# Sensores.net
KiCad netlist of a schematic drawn in Altium Designer
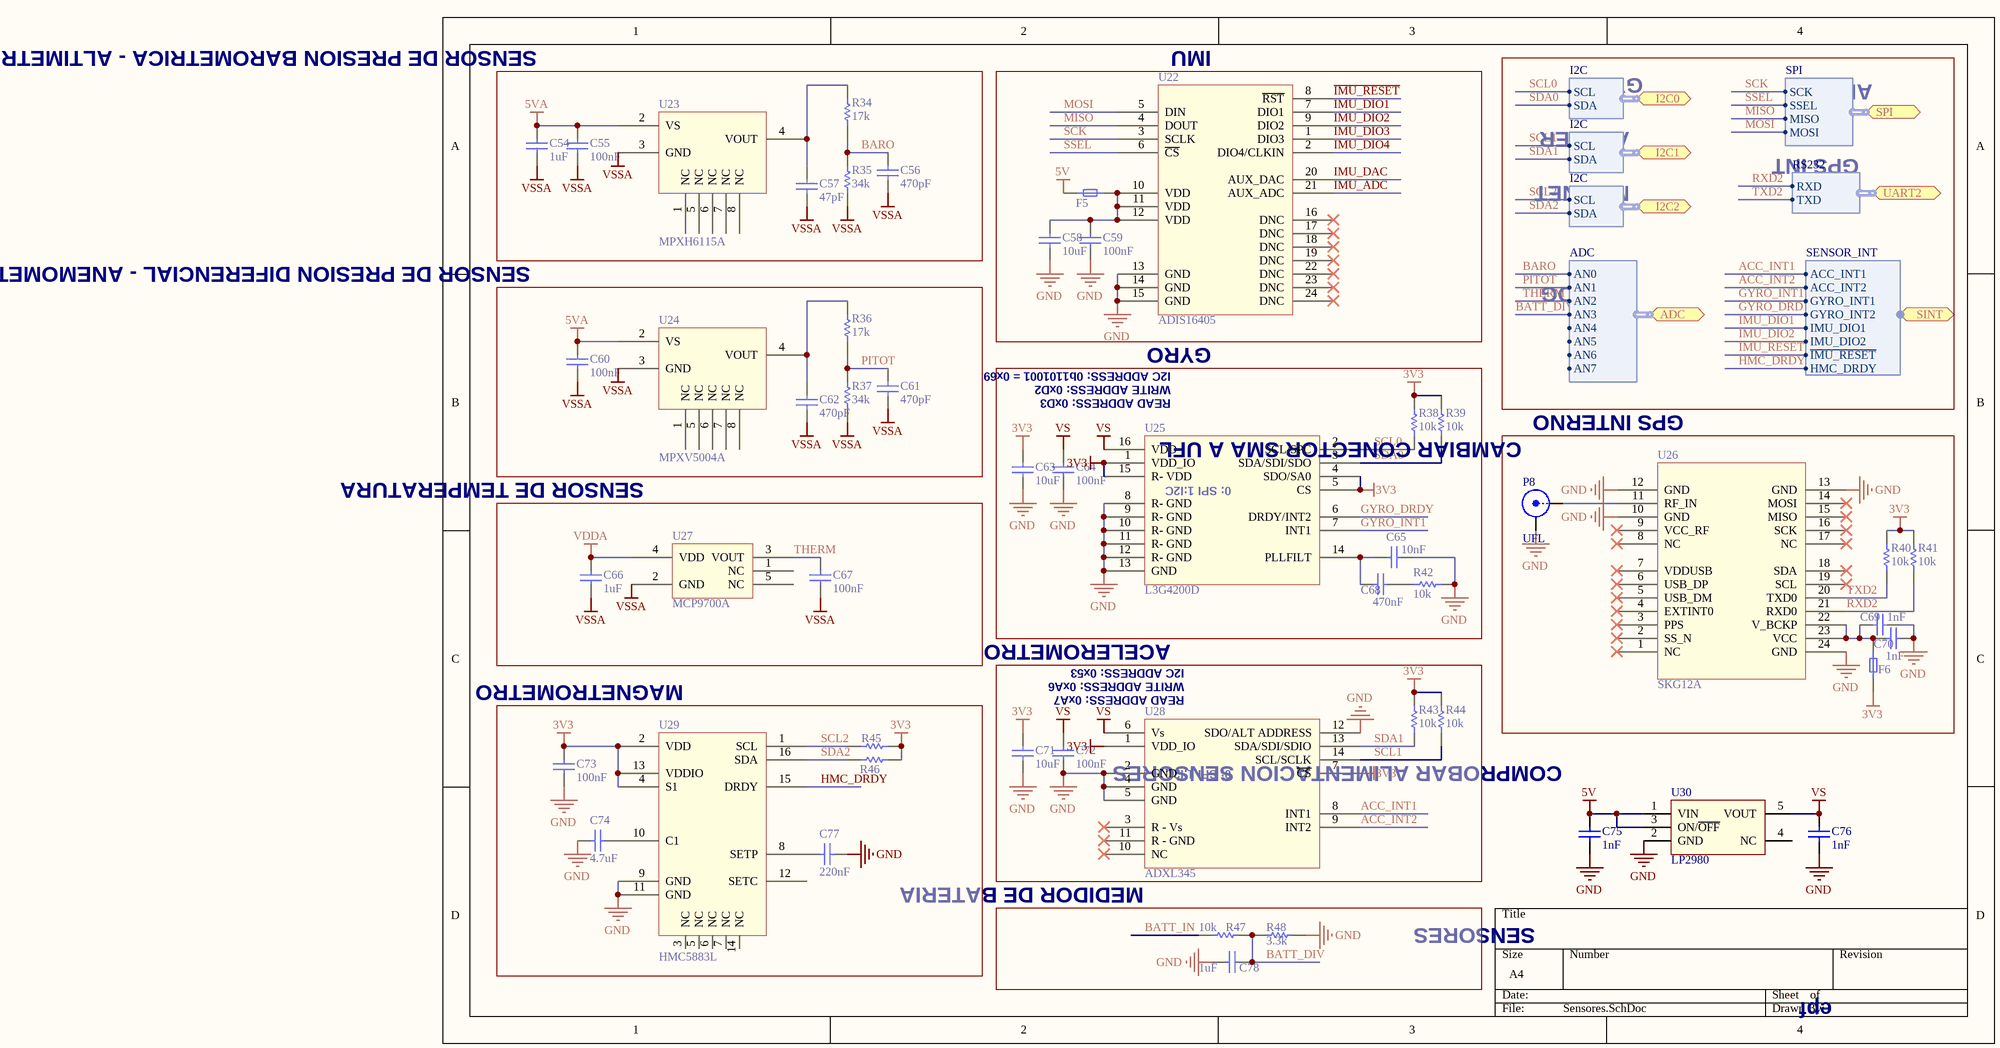
[diagram p0: Sensores.SchDoc]

(export (version "E")
  (design (tool "Eeschema 10.0.6"))
  (components
    (comp (ref "C54")
      (value "1uF")
      (footprint "CAP0402")
      (fields (field (name "Comment") "Capacitor"))
      (libsource (lib "epf") (part "Cap"))
    )
    (comp (ref "C55")
      (value "100nF")
      (footprint "CAP0402")
      (fields (field (name "Comment") "Capacitor"))
      (libsource (lib "epf") (part "Cap"))
    )
    (comp (ref "C56")
      (value "470pF")
      (footprint "CAP0402")
      (fields (field (name "Comment") "Capacitor"))
      (libsource (lib "epf") (part "Cap"))
    )
    (comp (ref "C57")
      (value "47pF")
      (footprint "CAP0402")
      (fields (field (name "Comment") "Capacitor"))
      (libsource (lib "epf") (part "Cap"))
    )
    (comp (ref "C58")
      (value "10uF")
      (footprint "CAP0402")
      (fields (field (name "Comment") "Capacitor"))
      (libsource (lib "epf") (part "Cap"))
    )
    (comp (ref "C59")
      (value "100nF")
      (footprint "CAP0402")
      (fields (field (name "Comment") "Capacitor"))
      (libsource (lib "epf") (part "Cap"))
    )
    (comp (ref "C60")
      (value "100nF")
      (footprint "CAP0402")
      (fields (field (name "Comment") "Capacitor"))
      (libsource (lib "epf") (part "Cap"))
    )
    (comp (ref "C61")
      (value "470pF")
      (footprint "CAP0402")
      (fields (field (name "Comment") "Capacitor"))
      (libsource (lib "epf") (part "Cap"))
    )
    (comp (ref "C62")
      (value "470pF")
      (footprint "CAP0402")
      (fields (field (name "Comment") "Capacitor"))
      (libsource (lib "epf") (part "Cap"))
    )
    (comp (ref "C63")
      (value "10uF")
      (footprint "CAP0402")
      (fields (field (name "Comment") "Capacitor"))
      (libsource (lib "epf") (part "Cap"))
    )
    (comp (ref "C64")
      (value "100nF")
      (footprint "CAP0402")
      (fields (field (name "Comment") "Capacitor"))
      (libsource (lib "epf") (part "Cap"))
    )
    (comp (ref "C65")
      (value "10nF")
      (footprint "CAP0402")
      (fields (field (name "Comment") "Capacitor"))
      (libsource (lib "epf") (part "Cap"))
    )
    (comp (ref "C66")
      (value "1uF")
      (footprint "CAP0402")
      (fields (field (name "Comment") "Capacitor"))
      (libsource (lib "epf") (part "Cap"))
    )
    (comp (ref "C67")
      (value "100nF")
      (footprint "CAP0402")
      (fields (field (name "Comment") "Capacitor"))
      (libsource (lib "epf") (part "Cap"))
    )
    (comp (ref "C68")
      (value "470nF")
      (footprint "CAP0402")
      (fields (field (name "Comment") "Capacitor"))
      (libsource (lib "epf") (part "Cap"))
    )
    (comp (ref "C69")
      (value "1nF")
      (footprint "CAP0402")
      (fields (field (name "Comment") "Capacitor"))
      (libsource (lib "epf") (part "Cap"))
    )
    (comp (ref "C70")
      (value "1nF")
      (footprint "CAP0402")
      (fields (field (name "Comment") "Capacitor"))
      (libsource (lib "epf") (part "Cap"))
    )
    (comp (ref "C71")
      (value "10uF")
      (footprint "CAP0402")
      (fields (field (name "Comment") "Capacitor"))
      (libsource (lib "epf") (part "Cap"))
    )
    (comp (ref "C72")
      (value "100nF")
      (footprint "CAP0402")
      (fields (field (name "Comment") "Capacitor"))
      (libsource (lib "epf") (part "Cap"))
    )
    (comp (ref "C73")
      (value "100nF")
      (footprint "CAP0402")
      (fields (field (name "Comment") "Capacitor"))
      (libsource (lib "epf") (part "Cap"))
    )
    (comp (ref "C74")
      (value "4.7uF")
      (footprint "CAP0402")
      (fields (field (name "Comment") "Capacitor"))
      (libsource (lib "epf") (part "Cap"))
    )
    (comp (ref "C75")
      (value "1nF")
      (footprint "CAP0402")
      (fields (field (name "Comment") "Capacitor"))
      (libsource (lib "epf") (part "Cap"))
    )
    (comp (ref "C76")
      (value "1nF")
      (footprint "CAP0402")
      (fields (field (name "Comment") "Capacitor"))
      (libsource (lib "epf") (part "Cap"))
    )
    (comp (ref "C77")
      (value "220nF")
      (footprint "CAP0402")
      (fields (field (name "Comment") "Capacitor"))
      (libsource (lib "epf") (part "Cap"))
    )
    (comp (ref "C78")
      (value "1uF")
      (footprint "CAP0402")
      (fields (field (name "Comment") "Capacitor"))
      (libsource (lib "epf") (part "Cap"))
    )
    (comp (ref "F5") (value "Ferrita") (footprint "IND0603") (libsource (lib "epf") (part "Ferrita")))
    (comp (ref "F6") (value "Ferrita") (footprint "IND0603") (libsource (lib "epf") (part "Ferrita")))
    (comp (ref "P8") (value "UFL") (footprint "UFL") (libsource (lib "epf") (part "UFL")))
    (comp (ref "R34")
      (value "17k")
      (footprint "RES0402")
      (fields (field (name "Comment") "Resistor"))
      (libsource (lib "epf") (part "Res"))
    )
    (comp (ref "R35")
      (value "34k")
      (footprint "RES0402")
      (fields (field (name "Comment") "Resistor"))
      (libsource (lib "epf") (part "Res"))
    )
    (comp (ref "R36")
      (value "17k")
      (footprint "RES0402")
      (fields (field (name "Comment") "Resistor"))
      (libsource (lib "epf") (part "Res"))
    )
    (comp (ref "R37")
      (value "34k")
      (footprint "RES0402")
      (fields (field (name "Comment") "Resistor"))
      (libsource (lib "epf") (part "Res"))
    )
    (comp (ref "R38")
      (value "10k")
      (footprint "RES0402")
      (fields (field (name "Comment") "Resistor"))
      (libsource (lib "epf") (part "Res"))
    )
    (comp (ref "R39")
      (value "10k")
      (footprint "RES0402")
      (fields (field (name "Comment") "Resistor"))
      (libsource (lib "epf") (part "Res"))
    )
    (comp (ref "R40")
      (value "10k")
      (footprint "RES0402")
      (fields (field (name "Comment") "Resistor"))
      (libsource (lib "epf") (part "Res"))
    )
    (comp (ref "R41")
      (value "10k")
      (footprint "RES0402")
      (fields (field (name "Comment") "Resistor"))
      (libsource (lib "epf") (part "Res"))
    )
    (comp (ref "R42")
      (value "10k")
      (footprint "RES0402")
      (fields (field (name "Comment") "Resistor"))
      (libsource (lib "epf") (part "Res"))
    )
    (comp (ref "R43")
      (value "10k")
      (footprint "RES0402")
      (fields (field (name "Comment") "Resistor"))
      (libsource (lib "epf") (part "Res"))
    )
    (comp (ref "R44")
      (value "10k")
      (footprint "RES0402")
      (fields (field (name "Comment") "Resistor"))
      (libsource (lib "epf") (part "Res"))
    )
    (comp (ref "R45") (value "Resistor") (footprint "RES0402") (libsource (lib "epf") (part "Res")))
    (comp (ref "R46") (value "Resistor") (footprint "RES0402") (libsource (lib "epf") (part "Res")))
    (comp (ref "R47")
      (value "10k")
      (footprint "RES0402")
      (fields (field (name "Comment") "Resistor"))
      (libsource (lib "epf") (part "Res"))
    )
    (comp (ref "R48")
      (value "3.3k")
      (footprint "RES0402")
      (fields (field (name "Comment") "Resistor"))
      (libsource (lib "epf") (part "Res"))
    )
    (comp (ref "U22") (value "ADIS16405") (footprint "ADIS16405") (libsource (lib "epf") (part "ADIS16405")))
    (comp (ref "U23")
      (value "MPXH6115A")
      (footprint "SSOP1317")
      (description "ABSOLUTE PRESSURE SENSOR")
      (libsource (lib "epf") (part "MPXH6115A"))
    )
    (comp (ref "U24")
      (value "MPXV5004A")
      (footprint "SSOP1351 - MPXV5004DP")
      (description "Differential Pressure Sensor")
      (libsource (lib "epf") (part "MPXV5004A"))
    )
    (comp (ref "U25")
      (value "L3G4200D")
      (footprint "QFN65P400X400-16 - L3G4200D")
      (description "3 axis gyroscope")
      (libsource (lib "epf") (part "L3G4200D"))
    )
    (comp (ref "U26")
      (value "SKG12A")
      (footprint "SKG12A")
      (description "MODULO GPS DE SkyNav")
      (libsource (lib "epf") (part "SKG12A"))
    )
    (comp (ref "U27")
      (value "MCP9700A")
      (footprint "SOT353-5AN")
      (description "SENSOR DE TEMPERATURA")
      (libsource (lib "epf") (part "MCP9700A"))
    )
    (comp (ref "U28")
      (value "ADXL345")
      (footprint "LGA80P500X300-14N")
      (description "Digital Accelerometer")
      (libsource (lib "epf") (part "ADXL345"))
    )
    (comp (ref "U29")
      (value "HMC5883L")
      (footprint "QFN50P300X300-16-HMC")
      (libsource (lib "epf") (part "HMC5883L"))
    )
    (comp (ref "U30")
      (value "LP2980")
      (footprint "SOT23-5BN")
      (description "Current 50mA")
      (libsource (lib "epf") (part "LP2980"))
    )
  )
  (nets
    (net (code "6") (name "/ACC_INT1") (class "Default")
      (node (ref "U28") (pin "8") (pinfunction "INT1_8") (pintype "passive"))
    )
    (net (code "7") (name "/ACC_INT2") (class "Default")
      (node (ref "U28") (pin "9") (pinfunction "INT2_9") (pintype "passive"))
    )
    (net (code "8") (name "/BARO") (class "Default")
      (node (ref "C56") (pin "2") (pinfunction "2_2") (pintype "passive"))
      (node (ref "R34") (pin "2") (pinfunction "2_2") (pintype "passive"))
      (node (ref "R35") (pin "1") (pinfunction "1_1") (pintype "passive"))
    )
    (net (code "9") (name "/BATT_DIV") (class "Default")
      (node (ref "C78") (pin "2") (pinfunction "2_2") (pintype "passive"))
      (node (ref "R47") (pin "2") (pinfunction "2_2") (pintype "passive"))
      (node (ref "R48") (pin "1") (pinfunction "1_1") (pintype "passive"))
    )
    (net (code "10") (name "/BATT_IN") (class "Default")
      (node (ref "R47") (pin "1") (pinfunction "1_1") (pintype "passive"))
    )
    (net (code "11") (name "/GYRO_DRDY") (class "Default")
      (node (ref "U25") (pin "6") (pinfunction "DRDY/INT2_6") (pintype "passive"))
    )
    (net (code "12") (name "/GYRO_INT1") (class "Default")
      (node (ref "U25") (pin "7") (pinfunction "INT1_7") (pintype "passive"))
    )
    (net (code "13") (name "/HMC_DRDY") (class "Default")
      (node (ref "U29") (pin "15") (pinfunction "DRDY_15") (pintype "passive"))
    )
    (net (code "14") (name "/IMU_ADC") (class "Default")
      (node (ref "U22") (pin "21") (pinfunction "AUX_ADC_21") (pintype "passive"))
    )
    (net (code "15") (name "/IMU_DAC") (class "Default")
      (node (ref "U22") (pin "20") (pinfunction "AUX_DAC_20") (pintype "passive"))
    )
    (net (code "16") (name "/IMU_DIO1") (class "Default")
      (node (ref "U22") (pin "7") (pinfunction "DIO1_7") (pintype "passive"))
    )
    (net (code "17") (name "/IMU_DIO2") (class "Default")
      (node (ref "U22") (pin "9") (pinfunction "DIO2_9") (pintype "passive"))
    )
    (net (code "18") (name "/IMU_DIO3") (class "Default")
      (node (ref "U22") (pin "1") (pinfunction "DIO3_1") (pintype "passive"))
    )
    (net (code "19") (name "/IMU_DIO4") (class "Default")
      (node (ref "U22") (pin "2") (pinfunction "DIO4/CLKIN_2") (pintype "passive"))
    )
    (net (code "20") (name "/IMU_RESET") (class "Default")
      (node (ref "U22") (pin "8") (pinfunction "RST_8") (pintype "passive"))
    )
    (net (code "21") (name "/MISO") (class "Default")
      (node (ref "U22") (pin "4") (pinfunction "DOUT_4") (pintype "passive"))
    )
    (net (code "22") (name "/MOSI") (class "Default")
      (node (ref "U22") (pin "5") (pinfunction "DIN_5") (pintype "passive"))
    )
    (net (code "23") (name "/PITOT") (class "Default")
      (node (ref "C61") (pin "2") (pinfunction "2_2") (pintype "passive"))
      (node (ref "R36") (pin "2") (pinfunction "2_2") (pintype "passive"))
      (node (ref "R37") (pin "1") (pinfunction "1_1") (pintype "passive"))
    )
    (net (code "24") (name "/RXD2") (class "Default")
      (node (ref "R41") (pin "2") (pinfunction "2_2") (pintype "passive"))
      (node (ref "U26") (pin "21") (pinfunction "RXD0_21") (pintype "passive"))
    )
    (net (code "25") (name "/SCK") (class "Default")
      (node (ref "U22") (pin "3") (pinfunction "SCLK_3") (pintype "passive"))
    )
    (net (code "26") (name "/SCL0") (class "Default")
      (node (ref "R38") (pin "2") (pinfunction "2_2") (pintype "passive"))
      (node (ref "U25") (pin "2") (pinfunction "SCL/SPC_2") (pintype "passive"))
    )
    (net (code "27") (name "/SCL1") (class "Default")
      (node (ref "R44") (pin "2") (pinfunction "2_2") (pintype "passive"))
      (node (ref "U28") (pin "14") (pinfunction "SCL/SCLK_14") (pintype "passive"))
    )
    (net (code "28") (name "/SCL2") (class "Default")
      (node (ref "R45") (pin "1") (pinfunction "1_1") (pintype "passive"))
      (node (ref "U29") (pin "1") (pinfunction "SCL_1") (pintype "passive"))
    )
    (net (code "29") (name "/SDA0") (class "Default")
      (node (ref "R39") (pin "2") (pinfunction "2_2") (pintype "passive"))
      (node (ref "U25") (pin "3") (pinfunction "SDA/SDI/SDO_3") (pintype "passive"))
    )
    (net (code "30") (name "/SDA1") (class "Default")
      (node (ref "R43") (pin "2") (pinfunction "2_2") (pintype "passive"))
      (node (ref "U28") (pin "13") (pinfunction "SDA/SDI/SDIO_13") (pintype "passive"))
    )
    (net (code "31") (name "/SDA2") (class "Default")
      (node (ref "R46") (pin "1") (pinfunction "1_1") (pintype "passive"))
      (node (ref "U29") (pin "16") (pinfunction "SDA_16") (pintype "passive"))
    )
    (net (code "32") (name "/SSEL") (class "Default")
      (node (ref "U22") (pin "6") (pinfunction "CS_6") (pintype "passive"))
    )
    (net (code "33") (name "/THERM") (class "Default")
      (node (ref "C67") (pin "2") (pinfunction "2_2") (pintype "passive"))
      (node (ref "U27") (pin "3") (pinfunction "VOUT_3") (pintype "passive"))
    )
    (net (code "34") (name "/TXD2") (class "Default")
      (node (ref "R40") (pin "2") (pinfunction "2_2") (pintype "passive"))
      (node (ref "U26") (pin "20") (pinfunction "TXD0_20") (pintype "passive"))
    )
    (net (code "40") (name "3V3") (class "Default")
      (node (ref "C63") (pin "2") (pinfunction "2_2") (pintype "passive"))
      (node (ref "C71") (pin "2") (pinfunction "2_2") (pintype "passive"))
      (node (ref "C73") (pin "1") (pinfunction "1_1") (pintype "passive"))
      (node (ref "F6") (pin "1") (pinfunction "1_1") (pintype "passive"))
      (node (ref "R38") (pin "1") (pinfunction "1_1") (pintype "passive"))
      (node (ref "R39") (pin "1") (pinfunction "1_1") (pintype "passive"))
      (node (ref "R40") (pin "1") (pinfunction "1_1") (pintype "passive"))
      (node (ref "R41") (pin "1") (pinfunction "1_1") (pintype "passive"))
      (node (ref "R43") (pin "1") (pinfunction "1_1") (pintype "passive"))
      (node (ref "R44") (pin "1") (pinfunction "1_1") (pintype "passive"))
      (node (ref "R45") (pin "2") (pinfunction "2_2") (pintype "passive"))
      (node (ref "R46") (pin "2") (pinfunction "2_2") (pintype "passive"))
      (node (ref "U25") (pin "1") (pinfunction "VDD_IO_1") (pintype "passive"))
      (node (ref "U25") (pin "15") (pinfunction "R-_VDD_15") (pintype "passive"))
      (node (ref "U25") (pin "4") (pinfunction "SDO/SA0_4") (pintype "passive"))
      (node (ref "U25") (pin "5") (pinfunction "CS_5") (pintype "passive"))
      (node (ref "U28") (pin "1") (pinfunction "VDD_IO_1") (pintype "passive"))
      (node (ref "U28") (pin "7") (pinfunction "CS_7") (pintype "passive"))
      (node (ref "U29") (pin "13") (pinfunction "VDDIO_13") (pintype "passive"))
      (node (ref "U29") (pin "2") (pinfunction "VDD_2") (pintype "passive"))
      (node (ref "U29") (pin "4") (pinfunction "S1_4") (pintype "passive"))
    )
    (net (code "41") (name "5V") (class "Default")
      (node (ref "C75") (pin "2") (pinfunction "2_2") (pintype "passive"))
      (node (ref "F5") (pin "1") (pinfunction "1_1") (pintype "passive"))
      (node (ref "U30") (pin "1") (pinfunction "VIN_1") (pintype "passive"))
      (node (ref "U30") (pin "3") (pinfunction "ON/~{OFF}_3") (pintype "passive"))
    )
    (net (code "42") (name "5VA") (class "Default")
      (node (ref "C54") (pin "2") (pinfunction "2_2") (pintype "passive"))
      (node (ref "C55") (pin "2") (pinfunction "2_2") (pintype "passive"))
      (node (ref "C60") (pin "2") (pinfunction "2_2") (pintype "passive"))
      (node (ref "U23") (pin "2") (pinfunction "VS_2") (pintype "passive"))
      (node (ref "U24") (pin "2") (pinfunction "VS_2") (pintype "passive"))
    )
    (net (code "43") (name "GND") (class "Default")
      (node (ref "C58") (pin "1") (pinfunction "1_1") (pintype "passive"))
      (node (ref "C59") (pin "1") (pinfunction "1_1") (pintype "passive"))
      (node (ref "C63") (pin "1") (pinfunction "1_1") (pintype "passive"))
      (node (ref "C64") (pin "1") (pinfunction "1_1") (pintype "passive"))
      (node (ref "C65") (pin "1") (pinfunction "1_1") (pintype "passive"))
      (node (ref "C69") (pin "1") (pinfunction "1_1") (pintype "passive"))
      (node (ref "C70") (pin "1") (pinfunction "1_1") (pintype "passive"))
      (node (ref "C71") (pin "1") (pinfunction "1_1") (pintype "passive"))
      (node (ref "C72") (pin "1") (pinfunction "1_1") (pintype "passive"))
      (node (ref "C73") (pin "2") (pinfunction "2_2") (pintype "passive"))
      (node (ref "C74") (pin "2") (pinfunction "2_2") (pintype "passive"))
      (node (ref "C75") (pin "1") (pinfunction "1_1") (pintype "passive"))
      (node (ref "C76") (pin "1") (pinfunction "1_1") (pintype "passive"))
      (node (ref "C77") (pin "1") (pinfunction "1_1") (pintype "passive"))
      (node (ref "C78") (pin "1") (pinfunction "1_1") (pintype "passive"))
      (node (ref "P8") (pin "2") (pinfunction "Y_2") (pintype "passive"))
      (node (ref "R42") (pin "2") (pinfunction "2_2") (pintype "passive"))
      (node (ref "R48") (pin "2") (pinfunction "2_2") (pintype "passive"))
      (node (ref "U22") (pin "13") (pinfunction "GND_13") (pintype "passive"))
      (node (ref "U22") (pin "14") (pinfunction "GND_14") (pintype "passive"))
      (node (ref "U22") (pin "15") (pinfunction "GND_15") (pintype "passive"))
      (node (ref "U25") (pin "10") (pinfunction "R-_GND_10") (pintype "passive"))
      (node (ref "U25") (pin "11") (pinfunction "R-_GND_11") (pintype "passive"))
      (node (ref "U25") (pin "12") (pinfunction "R-_GND_12") (pintype "passive"))
      (node (ref "U25") (pin "13") (pinfunction "GND_13") (pintype "passive"))
      (node (ref "U25") (pin "8") (pinfunction "R-_GND_8") (pintype "passive"))
      (node (ref "U25") (pin "9") (pinfunction "R-_GND_9") (pintype "passive"))
      (node (ref "U26") (pin "10") (pinfunction "GND_10") (pintype "passive"))
      (node (ref "U26") (pin "12") (pinfunction "GND_12") (pintype "passive"))
      (node (ref "U26") (pin "13") (pinfunction "GND_13") (pintype "passive"))
      (node (ref "U26") (pin "24") (pinfunction "GND_24") (pintype "passive"))
      (node (ref "U28") (pin "12") (pinfunction "SDO/ALT_ADDRESS_12") (pintype "passive"))
      (node (ref "U28") (pin "2") (pinfunction "GND_2") (pintype "passive"))
      (node (ref "U28") (pin "4") (pinfunction "GND_4") (pintype "passive"))
      (node (ref "U28") (pin "5") (pinfunction "GND_5") (pintype "passive"))
      (node (ref "U29") (pin "11") (pinfunction "GND_11") (pintype "passive"))
      (node (ref "U29") (pin "9") (pinfunction "GND_9") (pintype "passive"))
      (node (ref "U30") (pin "2") (pinfunction "GND_2") (pintype "passive"))
    )
    (net (code "44") (name "Net-(C58-Pad2)") (class "Default")
      (node (ref "C58") (pin "2") (pinfunction "2_2") (pintype "passive"))
      (node (ref "C59") (pin "2") (pinfunction "2_2") (pintype "passive"))
      (node (ref "F5") (pin "2") (pinfunction "2_2") (pintype "passive"))
      (node (ref "U22") (pin "10") (pinfunction "VDD_10") (pintype "passive"))
      (node (ref "U22") (pin "11") (pinfunction "VDD_11") (pintype "passive"))
      (node (ref "U22") (pin "12") (pinfunction "VDD_12") (pintype "passive"))
    )
    (net (code "45") (name "Net-(C68-Pad1)") (class "Default")
      (node (ref "C68") (pin "1") (pinfunction "1_1") (pintype "passive"))
      (node (ref "R42") (pin "1") (pinfunction "1_1") (pintype "passive"))
    )
    (net (code "46") (name "Net-(P8-X)") (class "Default")
      (node (ref "P8") (pin "1") (pinfunction "X_1") (pintype "passive"))
      (node (ref "U26") (pin "11") (pinfunction "RF_IN_11") (pintype "passive"))
    )
    (net (code "47") (name "Net-(U23-VOUT)") (class "Default")
      (node (ref "C57") (pin "2") (pinfunction "2_2") (pintype "passive"))
      (node (ref "R34") (pin "1") (pinfunction "1_1") (pintype "passive"))
      (node (ref "U23") (pin "4") (pinfunction "VOUT_4") (pintype "passive"))
    )
    (net (code "48") (name "Net-(U24-VOUT)") (class "Default")
      (node (ref "C62") (pin "2") (pinfunction "2_2") (pintype "passive"))
      (node (ref "R36") (pin "1") (pinfunction "1_1") (pintype "passive"))
      (node (ref "U24") (pin "4") (pinfunction "VOUT_4") (pintype "passive"))
    )
    (net (code "49") (name "Net-(U25-PLLFILT)") (class "Default")
      (node (ref "C65") (pin "2") (pinfunction "2_2") (pintype "passive"))
      (node (ref "C68") (pin "2") (pinfunction "2_2") (pintype "passive"))
      (node (ref "U25") (pin "14") (pinfunction "PLLFILT_14") (pintype "passive"))
    )
    (net (code "50") (name "Net-(U26-VCC)") (class "Default")
      (node (ref "C69") (pin "2") (pinfunction "2_2") (pintype "passive"))
      (node (ref "C70") (pin "2") (pinfunction "2_2") (pintype "passive"))
      (node (ref "F6") (pin "2") (pinfunction "2_2") (pintype "passive"))
      (node (ref "U26") (pin "22") (pinfunction "V_BCKP_22") (pintype "passive"))
      (node (ref "U26") (pin "23") (pinfunction "VCC_23") (pintype "passive"))
    )
    (net (code "51") (name "Net-(U29-C1)") (class "Default")
      (node (ref "C74") (pin "1") (pinfunction "1_1") (pintype "passive"))
      (node (ref "U29") (pin "10") (pinfunction "C1_10") (pintype "passive"))
    )
    (net (code "52") (name "Net-(U29-SETP)") (class "Default")
      (node (ref "C77") (pin "2") (pinfunction "2_2") (pintype "passive"))
      (node (ref "U29") (pin "8") (pinfunction "SETP_8") (pintype "passive"))
    )
    (net (code "53") (name "VDDA") (class "Default")
      (node (ref "C66") (pin "2") (pinfunction "2_2") (pintype "passive"))
      (node (ref "U27") (pin "4") (pinfunction "VDD_4") (pintype "passive"))
    )
    (net (code "54") (name "VS") (class "Default")
      (node (ref "C64") (pin "2") (pinfunction "2_2") (pintype "passive"))
      (node (ref "C72") (pin "2") (pinfunction "2_2") (pintype "passive"))
      (node (ref "C76") (pin "2") (pinfunction "2_2") (pintype "passive"))
      (node (ref "U25") (pin "16") (pinfunction "VDD_16") (pintype "passive"))
      (node (ref "U28") (pin "6") (pinfunction "Vs_6") (pintype "passive"))
      (node (ref "U30") (pin "5") (pinfunction "VOUT_5") (pintype "passive"))
    )
    (net (code "55") (name "VSSA") (class "Default")
      (node (ref "C54") (pin "1") (pinfunction "1_1") (pintype "passive"))
      (node (ref "C55") (pin "1") (pinfunction "1_1") (pintype "passive"))
      (node (ref "C56") (pin "1") (pinfunction "1_1") (pintype "passive"))
      (node (ref "C57") (pin "1") (pinfunction "1_1") (pintype "passive"))
      (node (ref "C60") (pin "1") (pinfunction "1_1") (pintype "passive"))
      (node (ref "C61") (pin "1") (pinfunction "1_1") (pintype "passive"))
      (node (ref "C62") (pin "1") (pinfunction "1_1") (pintype "passive"))
      (node (ref "C66") (pin "1") (pinfunction "1_1") (pintype "passive"))
      (node (ref "C67") (pin "1") (pinfunction "1_1") (pintype "passive"))
      (node (ref "R35") (pin "2") (pinfunction "2_2") (pintype "passive"))
      (node (ref "R37") (pin "2") (pinfunction "2_2") (pintype "passive"))
      (node (ref "U23") (pin "3") (pinfunction "GND_3") (pintype "passive"))
      (node (ref "U24") (pin "3") (pinfunction "GND_3") (pintype "passive"))
      (node (ref "U27") (pin "2") (pinfunction "GND_2") (pintype "passive"))
    )
    (net (code "56") (name "unconnected-(U22-DNC-Pad16)") (class "Default")
      (node (ref "U22") (pin "16") (pinfunction "DNC_16") (pintype "passive+no_connect"))
    )
    (net (code "57") (name "unconnected-(U22-DNC-Pad17)") (class "Default")
      (node (ref "U22") (pin "17") (pinfunction "DNC_17") (pintype "passive+no_connect"))
    )
    (net (code "58") (name "unconnected-(U22-DNC-Pad18)") (class "Default")
      (node (ref "U22") (pin "18") (pinfunction "DNC_18") (pintype "passive+no_connect"))
    )
    (net (code "59") (name "unconnected-(U22-DNC-Pad19)") (class "Default")
      (node (ref "U22") (pin "19") (pinfunction "DNC_19") (pintype "passive+no_connect"))
    )
    (net (code "60") (name "unconnected-(U22-DNC-Pad22)") (class "Default")
      (node (ref "U22") (pin "22") (pinfunction "DNC_22") (pintype "passive+no_connect"))
    )
    (net (code "61") (name "unconnected-(U22-DNC-Pad23)") (class "Default")
      (node (ref "U22") (pin "23") (pinfunction "DNC_23") (pintype "passive+no_connect"))
    )
    (net (code "62") (name "unconnected-(U22-DNC-Pad24)") (class "Default")
      (node (ref "U22") (pin "24") (pinfunction "DNC_24") (pintype "passive+no_connect"))
    )
    (net (code "63") (name "unconnected-(U23-NC-Pad1)") (class "Default")
      (node (ref "U23") (pin "1") (pinfunction "NC_1") (pintype "passive"))
    )
    (net (code "64") (name "unconnected-(U23-NC-Pad5)") (class "Default")
      (node (ref "U23") (pin "5") (pinfunction "NC_5") (pintype "passive"))
    )
    (net (code "65") (name "unconnected-(U23-NC-Pad6)") (class "Default")
      (node (ref "U23") (pin "6") (pinfunction "NC_6") (pintype "passive"))
    )
    (net (code "66") (name "unconnected-(U23-NC-Pad7)") (class "Default")
      (node (ref "U23") (pin "7") (pinfunction "NC_7") (pintype "passive"))
    )
    (net (code "67") (name "unconnected-(U23-NC-Pad8)") (class "Default")
      (node (ref "U23") (pin "8") (pinfunction "NC_8") (pintype "passive"))
    )
    (net (code "68") (name "unconnected-(U24-NC-Pad1)") (class "Default")
      (node (ref "U24") (pin "1") (pinfunction "NC_1") (pintype "passive"))
    )
    (net (code "69") (name "unconnected-(U24-NC-Pad5)") (class "Default")
      (node (ref "U24") (pin "5") (pinfunction "NC_5") (pintype "passive"))
    )
    (net (code "70") (name "unconnected-(U24-NC-Pad6)") (class "Default")
      (node (ref "U24") (pin "6") (pinfunction "NC_6") (pintype "passive"))
    )
    (net (code "71") (name "unconnected-(U24-NC-Pad7)") (class "Default")
      (node (ref "U24") (pin "7") (pinfunction "NC_7") (pintype "passive"))
    )
    (net (code "72") (name "unconnected-(U24-NC-Pad8)") (class "Default")
      (node (ref "U24") (pin "8") (pinfunction "NC_8") (pintype "passive"))
    )
    (net (code "73") (name "unconnected-(U26-EXTINT0-Pad4)") (class "Default")
      (node (ref "U26") (pin "4") (pinfunction "EXTINT0_4") (pintype "passive+no_connect"))
    )
    (net (code "74") (name "unconnected-(U26-MISO-Pad15)") (class "Default")
      (node (ref "U26") (pin "15") (pinfunction "MISO_15") (pintype "passive+no_connect"))
    )
    (net (code "75") (name "unconnected-(U26-MOSI-Pad14)") (class "Default")
      (node (ref "U26") (pin "14") (pinfunction "MOSI_14") (pintype "passive+no_connect"))
    )
    (net (code "76") (name "unconnected-(U26-NC-Pad1)") (class "Default")
      (node (ref "U26") (pin "1") (pinfunction "NC_1") (pintype "passive+no_connect"))
    )
    (net (code "77") (name "unconnected-(U26-NC-Pad8)") (class "Default")
      (node (ref "U26") (pin "8") (pinfunction "NC_8") (pintype "passive+no_connect"))
    )
    (net (code "78") (name "unconnected-(U26-NC-Pad17)") (class "Default")
      (node (ref "U26") (pin "17") (pinfunction "NC_17") (pintype "passive+no_connect"))
    )
    (net (code "79") (name "unconnected-(U26-PPS-Pad3)") (class "Default")
      (node (ref "U26") (pin "3") (pinfunction "PPS_3") (pintype "passive+no_connect"))
    )
    (net (code "80") (name "unconnected-(U26-SCK-Pad16)") (class "Default")
      (node (ref "U26") (pin "16") (pinfunction "SCK_16") (pintype "passive+no_connect"))
    )
    (net (code "81") (name "unconnected-(U26-SCL-Pad19)") (class "Default")
      (node (ref "U26") (pin "19") (pinfunction "SCL_19") (pintype "passive+no_connect"))
    )
    (net (code "82") (name "unconnected-(U26-SDA-Pad18)") (class "Default")
      (node (ref "U26") (pin "18") (pinfunction "SDA_18") (pintype "passive+no_connect"))
    )
    (net (code "83") (name "unconnected-(U26-SS_N-Pad2)") (class "Default")
      (node (ref "U26") (pin "2") (pinfunction "SS_N_2") (pintype "passive+no_connect"))
    )
    (net (code "84") (name "unconnected-(U26-USB_DM-Pad5)") (class "Default")
      (node (ref "U26") (pin "5") (pinfunction "USB_DM_5") (pintype "passive+no_connect"))
    )
    (net (code "85") (name "unconnected-(U26-USB_DP-Pad6)") (class "Default")
      (node (ref "U26") (pin "6") (pinfunction "USB_DP_6") (pintype "passive+no_connect"))
    )
    (net (code "86") (name "unconnected-(U26-VCC_RF-Pad9)") (class "Default")
      (node (ref "U26") (pin "9") (pinfunction "VCC_RF_9") (pintype "passive+no_connect"))
    )
    (net (code "87") (name "unconnected-(U26-VDDUSB-Pad7)") (class "Default")
      (node (ref "U26") (pin "7") (pinfunction "VDDUSB_7") (pintype "passive+no_connect"))
    )
    (net (code "88") (name "unconnected-(U27-NC-Pad1)") (class "Default")
      (node (ref "U27") (pin "1") (pinfunction "NC_1") (pintype "passive"))
    )
    (net (code "89") (name "unconnected-(U27-NC-Pad5)") (class "Default")
      (node (ref "U27") (pin "5") (pinfunction "NC_5") (pintype "passive"))
    )
    (net (code "90") (name "unconnected-(U28-NC-Pad10)") (class "Default")
      (node (ref "U28") (pin "10") (pinfunction "NC_10") (pintype "passive+no_connect"))
    )
    (net (code "91") (name "unconnected-(U28-R_-_GND-Pad11)") (class "Default")
      (node (ref "U28") (pin "11") (pinfunction "R_-_GND_11") (pintype "passive+no_connect"))
    )
    (net (code "92") (name "unconnected-(U28-R_-_Vs-Pad3)") (class "Default")
      (node (ref "U28") (pin "3") (pinfunction "R_-_Vs_3") (pintype "passive+no_connect"))
    )
    (net (code "93") (name "unconnected-(U29-NC-Pad3)") (class "Default")
      (node (ref "U29") (pin "3") (pinfunction "NC_3") (pintype "passive"))
    )
    (net (code "94") (name "unconnected-(U29-NC-Pad5)") (class "Default")
      (node (ref "U29") (pin "5") (pinfunction "NC_5") (pintype "passive"))
    )
    (net (code "95") (name "unconnected-(U29-NC-Pad6)") (class "Default")
      (node (ref "U29") (pin "6") (pinfunction "NC_6") (pintype "passive"))
    )
    (net (code "96") (name "unconnected-(U29-NC-Pad7)") (class "Default")
      (node (ref "U29") (pin "7") (pinfunction "NC_7") (pintype "passive"))
    )
    (net (code "97") (name "unconnected-(U29-NC-Pad14)") (class "Default")
      (node (ref "U29") (pin "14") (pinfunction "NC_14") (pintype "passive"))
    )
    (net (code "98") (name "unconnected-(U29-SETC-Pad12)") (class "Default")
      (node (ref "U29") (pin "12") (pinfunction "SETC_12") (pintype "passive"))
    )
    (net (code "99") (name "unconnected-(U30-NC-Pad4)") (class "Default")
      (node (ref "U30") (pin "4") (pinfunction "NC_4") (pintype "passive"))
    )
  )
)
